# Camera_Module.net
KiCad netlist of a schematic drawn in Altium Designer
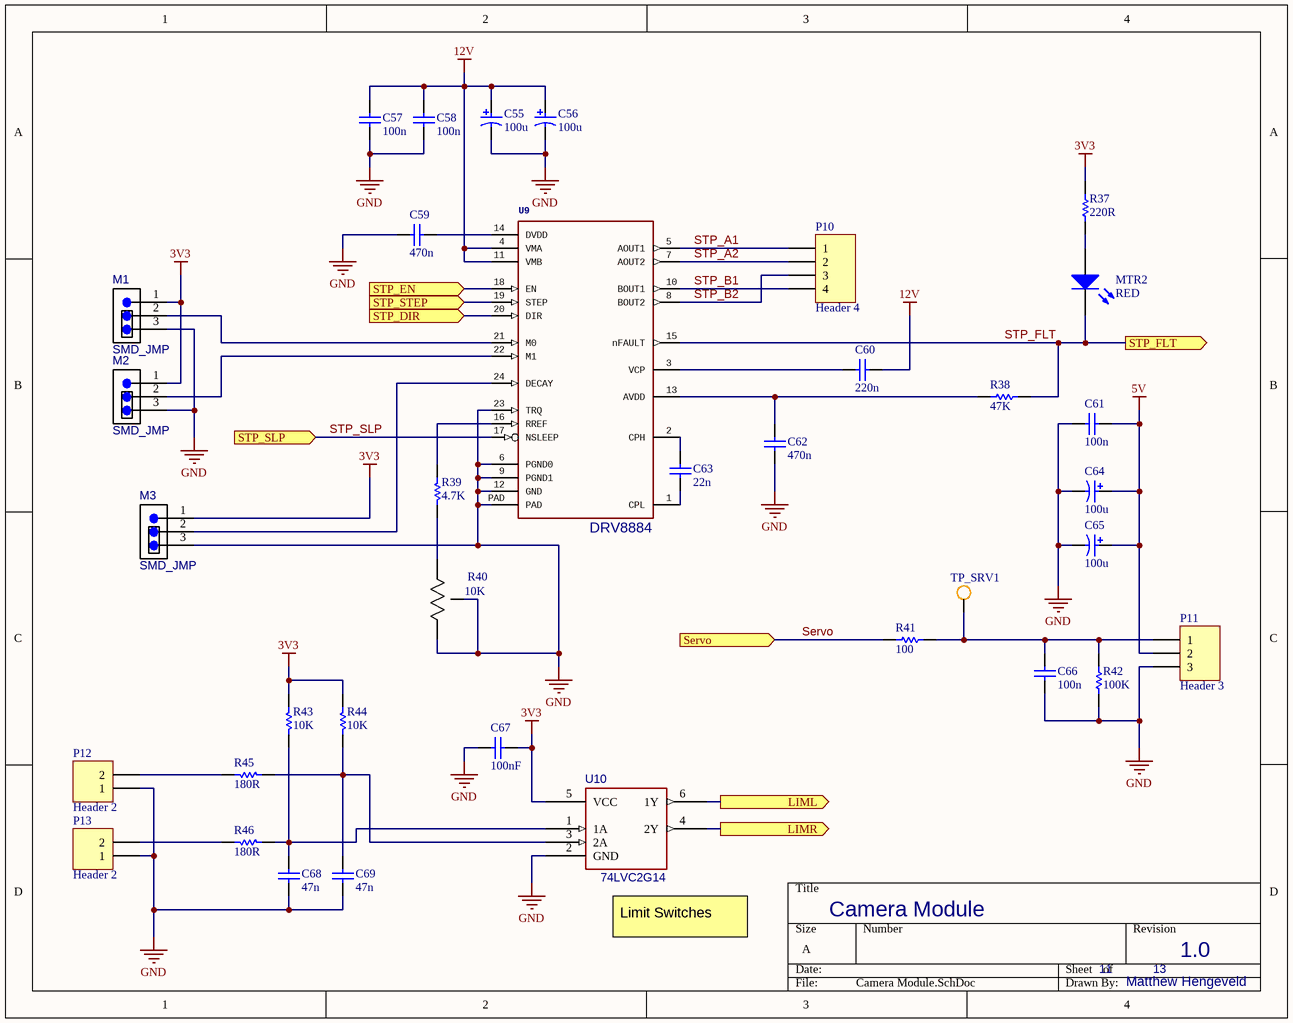
[diagram p0: Camera Module.SchDoc]

(export (version "E")
  (design (tool "Eeschema 10.0.6"))
  (components
    (comp (ref "C55")
      (value "100u")
      (footprint "SMD-CAP-0606")
      (fields (field (name "PARTNUMBER") "UUD1V101MNL1GS") (field (name "MANUFACTURER") "Nichicon"))
      (libsource (lib "Hengeveld") (part "CAP-EL-0606-SMD"))
    )
    (comp (ref "C56")
      (value "100u")
      (footprint "SMD-CAP-0606")
      (fields (field (name "PARTNUMBER") "UUD1V101MNL1GS") (field (name "MANUFACTURER") "Nichicon"))
      (libsource (lib "Hengeveld") (part "CAP-EL-0606-SMD"))
    )
    (comp (ref "C57")
      (value "100n")
      (footprint "CAPC1608X87X35LL15T15")
      (fields (field (name "PART NUMBER") "C0603X104K5RACTU") (field (name "MANUFACTURER") "Kemet"))
      (libsource (lib "Altium Content Vault") (part "CAP"))
    )
    (comp (ref "C58")
      (value "100n")
      (footprint "CAPC1608X87X35LL15T15")
      (fields (field (name "PART NUMBER") "C0603X104K5RACTU") (field (name "MANUFACTURER") "Kemet"))
      (libsource (lib "Altium Content Vault") (part "CAP"))
    )
    (comp (ref "C59")
      (value "470n")
      (footprint "CAPC1608X87X35LL15T15")
      (fields (field (name "PART NUMBER") "C0603X104K5RACTU") (field (name "MANUFACTURER") "Kemet"))
      (libsource (lib "Altium Content Vault") (part "CAP"))
    )
    (comp (ref "C60")
      (value "220n")
      (footprint "CAPC1608X87X35LL15T15")
      (fields (field (name "PART NUMBER") "C0603X104K5RACTU") (field (name "MANUFACTURER") "Kemet"))
      (libsource (lib "Altium Content Vault") (part "CAP"))
    )
    (comp (ref "C61")
      (value "100n")
      (footprint "CAPC1608X87X35LL15T15")
      (fields (field (name "PART NUMBER") "C0603X104K5RACTU") (field (name "MANUFACTURER") "Kemet"))
      (libsource (lib "Altium Content Vault") (part "CAP"))
    )
    (comp (ref "C62")
      (value "470n")
      (footprint "CAPC1608X90X35LL10T15")
      (fields (field (name "MANUFACTURER") "Murata") (field (name "PART NUMBER") "GRM188R71C474KA88D"))
      (libsource (lib "Altium Content Vault") (part "CAP"))
    )
    (comp (ref "C63")
      (value "22n")
      (footprint "CAPC1608X87X35LL15T15")
      (fields (field (name "MANUFACTURER") "Kemet") (field (name "PART NUMBER") "C0603C103K1RACTU"))
      (libsource (lib "Altium Content Vault") (part "CAP"))
    )
    (comp (ref "C64")
      (value "100u")
      (footprint "SMD-CAP-0606")
      (fields (field (name "PARTNUMBER") "UUD1V101MNL1GS") (field (name "MANUFACTURER") "Nichicon"))
      (libsource (lib "Hengeveld") (part "CAP-EL-0606-SMD"))
    )
    (comp (ref "C65")
      (value "100u")
      (footprint "SMD-CAP-0606")
      (fields (field (name "PARTNUMBER") "UUD1V101MNL1GS") (field (name "MANUFACTURER") "Nichicon"))
      (libsource (lib "Hengeveld") (part "CAP-EL-0606-SMD"))
    )
    (comp (ref "C66")
      (value "100n")
      (footprint "CAPC1608X90X35LL10T15")
      (fields (field (name "MANUFACTURER") "Murata") (field (name "PART NUMBER") "GRM188R71C474KA88D"))
      (libsource (lib "Altium Content Vault") (part "CAP"))
    )
    (comp (ref "C67")
      (value "100nF")
      (footprint "CAPC1608X92X38LL15T08")
      (fields (field (name "PART NUMBER") "VJ0603Y104KNXAO") (field (name "MANUFACTURER") "Vitramon"))
      (libsource (lib "Altium Content Vault") (part "CAP"))
    )
    (comp (ref "C68")
      (value "47n")
      (footprint "CAPC1608X87X35LL15T15")
      (fields (field (name "PART NUMBER") "C0603X104K5RACTU") (field (name "MANUFACTURER") "Kemet"))
      (libsource (lib "Altium Content Vault") (part "CAP"))
    )
    (comp (ref "C69")
      (value "47n")
      (footprint "CAPC1608X87X35LL15T15")
      (fields (field (name "PART NUMBER") "C0603X104K5RACTU") (field (name "MANUFACTURER") "Kemet"))
      (libsource (lib "Altium Content Vault") (part "CAP"))
    )
    (comp (ref "M1")
      (value "SMD_JMP")
      (footprint "0603_JUMPER")
      (libsource (lib "Hengeveld") (part "SMD_JMP"))
    )
    (comp (ref "M2")
      (value "SMD_JMP")
      (footprint "0603_JUMPER")
      (libsource (lib "Hengeveld") (part "SMD_JMP"))
    )
    (comp (ref "M3")
      (value "SMD_JMP")
      (footprint "0603_JUMPER")
      (libsource (lib "Hengeveld") (part "SMD_JMP"))
    )
    (comp (ref "MTR2")
      (value "RED")
      (footprint "0805_A")
      (description "SMD mono-color Chip LED, WL-SMCW, Red")
      (fields (field (name "PARTNUMBER") "150080RS75000") (field (name "MANUFACTURER") "Wuerth Elektronik"))
      (libsource (lib "Altium Content Vault") (part "WE-LED_K1A2-2"))
    )
    (comp (ref "P10")
      (value "Header 4")
      (footprint "HDR1X4")
      (description "Header, 4-Pin")
      (fields (field (name "PUBLISHER") "Altium Limited"))
      (libsource (lib "Hengeveld") (part "Header 4"))
    )
    (comp (ref "P11")
      (value "Header 3")
      (footprint "HDR1X3")
      (description "Header, 3-Pin")
      (fields (field (name "PUBLISHER") "Altium Limited"))
      (libsource (lib "Hengeveld") (part "Header 3"))
    )
    (comp (ref "P12")
      (value "Header 2")
      (footprint "HDR1X2")
      (description "Header, 2-Pin")
      (fields (field (name "PUBLISHER") "Altium Limited"))
      (libsource (lib "Hengeveld") (part "Header 2"))
    )
    (comp (ref "P13")
      (value "Header 2")
      (footprint "HDR1X2")
      (description "Header, 2-Pin")
      (fields (field (name "PUBLISHER") "Altium Limited"))
      (libsource (lib "Hengeveld") (part "Header 2"))
    )
    (comp (ref "R37")
      (value "220R")
      (footprint "RESC1608X55X30LL15T15")
      (fields (field (name "MANUFACTURER") "Panasonic") (field (name "PART NUMBER") "ERJ-3GEYJ103V"))
      (libsource (lib "Altium Content Vault") (part "RES"))
    )
    (comp (ref "R38")
      (value "47K")
      (footprint "RESC1608X55X30LL15T15")
      (fields (field (name "MANUFACTURER") "Panasonic") (field (name "PART NUMBER") "ERJ-3GEYJ103V"))
      (libsource (lib "Altium Content Vault") (part "RES"))
    )
    (comp (ref "R39")
      (value "4.7K")
      (footprint "RESC1608X55X30LL15T15")
      (fields (field (name "MANUFACTURER") "Panasonic") (field (name "PART NUMBER") "ERJ-3GEYJ103V"))
      (libsource (lib "Altium Content Vault") (part "RES"))
    )
    (comp (ref "R40") (value "10K") (footprint "TRIMMER-TC33") (libsource (lib "Hengeveld") (part "Trimmer")))
    (comp (ref "R41")
      (value "100")
      (footprint "RESC1608X55X30LL15T15")
      (fields (field (name "MANUFACTURER") "Panasonic") (field (name "PART NUMBER") "ERJ-3GEYJ103V"))
      (libsource (lib "Altium Content Vault") (part "RES"))
    )
    (comp (ref "R42")
      (value "100K")
      (footprint "RESC1608X55X30LL15T15")
      (fields (field (name "MANUFACTURER") "Panasonic") (field (name "PART NUMBER") "ERJ-3GEYJ103V"))
      (libsource (lib "Altium Content Vault") (part "RES"))
    )
    (comp (ref "R43")
      (value "10K")
      (footprint "RESC1608X55X30LL15T15")
      (fields (field (name "MANUFACTURER") "Panasonic") (field (name "PART NUMBER") "ERJ-3GEYJ103V"))
      (libsource (lib "Altium Content Vault") (part "RES"))
    )
    (comp (ref "R44")
      (value "10K")
      (footprint "RESC1608X55X30LL15T15")
      (fields (field (name "MANUFACTURER") "Panasonic") (field (name "PART NUMBER") "ERJ-3GEYJ103V"))
      (libsource (lib "Altium Content Vault") (part "RES"))
    )
    (comp (ref "R45")
      (value "180R")
      (footprint "RESC1608X55X30LL15T15")
      (fields (field (name "MANUFACTURER") "Panasonic") (field (name "PART NUMBER") "ERJ-3GEYJ103V"))
      (libsource (lib "Altium Content Vault") (part "RES"))
    )
    (comp (ref "R46")
      (value "180R")
      (footprint "RESC1608X55X30LL15T15")
      (fields (field (name "MANUFACTURER") "Panasonic") (field (name "PART NUMBER") "ERJ-3GEYJ103V"))
      (libsource (lib "Altium Content Vault") (part "RES"))
    )
    (comp (ref "TP_SRV1")
      (value "Test point")
      (footprint "SMD Test Hook")
      (libsource (lib "Hengeveld") (part "Test Point"))
    )
    (comp (ref "U9") (value "DRV8884") (footprint "TI-PWP24") (libsource (lib "Hengeveld") (part "DRV8884")))
    (comp (ref "U10")
      (value "74LVC2G14")
      (footprint "ONSC-SOT-363-6-419B-02_V")
      (libsource (lib "Hengeveld") (part "74LVC2G14"))
    )
  )
  (nets
    (net (code "1") (name "/LIML") (class "Default")
      (node (ref "U10") (pin "6") (pinfunction "1Y_6") (pintype "output"))
    )
    (net (code "2") (name "/LIMR") (class "Default")
      (node (ref "U10") (pin "4") (pinfunction "2Y_4") (pintype "output"))
    )
    (net (code "3") (name "/STP_A1") (class "Default")
      (node (ref "P10") (pin "1") (pinfunction "1_1") (pintype "passive"))
      (node (ref "U9") (pin "5") (pinfunction "AOUT1_5") (pintype "output"))
    )
    (net (code "4") (name "/STP_A2") (class "Default")
      (node (ref "P10") (pin "2") (pinfunction "2_2") (pintype "passive"))
      (node (ref "U9") (pin "7") (pinfunction "AOUT2_7") (pintype "output"))
    )
    (net (code "5") (name "/STP_B1") (class "Default")
      (node (ref "P10") (pin "4") (pinfunction "4_4") (pintype "passive"))
      (node (ref "U9") (pin "10") (pinfunction "BOUT1_10") (pintype "output"))
    )
    (net (code "6") (name "/STP_B2") (class "Default")
      (node (ref "P10") (pin "3") (pinfunction "3_3") (pintype "passive"))
      (node (ref "U9") (pin "8") (pinfunction "BOUT2_8") (pintype "output"))
    )
    (net (code "7") (name "/STP_DIR") (class "Default")
      (node (ref "U9") (pin "20") (pinfunction "DIR_20") (pintype "input"))
    )
    (net (code "8") (name "/STP_EN") (class "Default")
      (node (ref "U9") (pin "18") (pinfunction "EN_18") (pintype "input"))
    )
    (net (code "9") (name "/STP_FLT") (class "Default")
      (node (ref "MTR2") (pin "1") (pinfunction "K_1") (pintype "passive"))
      (node (ref "R38") (pin "2") (pinfunction "2_2") (pintype "passive"))
      (node (ref "U9") (pin "15") (pinfunction "nFAULT_15") (pintype "output"))
    )
    (net (code "10") (name "/STP_SLP") (class "Default")
      (node (ref "U9") (pin "17") (pinfunction "NSLEEP_17") (pintype "input"))
    )
    (net (code "11") (name "/STP_STEP") (class "Default")
      (node (ref "U9") (pin "19") (pinfunction "STEP_19") (pintype "input"))
    )
    (net (code "12") (name "/Servo") (class "Default")
      (node (ref "R41") (pin "2") (pinfunction "2_2") (pintype "passive"))
    )
    (net (code "13") (name "3V3") (class "Default")
      (node (ref "C67") (pin "2") (pinfunction "2_2") (pintype "passive"))
      (node (ref "M1") (pin "1") (pinfunction "1_1") (pintype "passive"))
      (node (ref "M2") (pin "1") (pinfunction "1_1") (pintype "passive"))
      (node (ref "M3") (pin "1") (pinfunction "1_1") (pintype "passive"))
      (node (ref "R37") (pin "1") (pinfunction "1_1") (pintype "passive"))
      (node (ref "R43") (pin "1") (pinfunction "1_1") (pintype "passive"))
      (node (ref "R44") (pin "1") (pinfunction "1_1") (pintype "passive"))
      (node (ref "U10") (pin "5") (pinfunction "VCC_5") (pintype "power_in"))
    )
    (net (code "14") (name "5V") (class "Default")
      (node (ref "C61") (pin "1") (pinfunction "1_1") (pintype "passive"))
      (node (ref "C64") (pin "1") (pinfunction "1_1") (pintype "passive"))
      (node (ref "C65") (pin "1") (pinfunction "1_1") (pintype "passive"))
      (node (ref "P11") (pin "2") (pinfunction "2_2") (pintype "passive"))
    )
    (net (code "15") (name "12V") (class "Default")
      (node (ref "C55") (pin "1") (pinfunction "1_1") (pintype "passive"))
      (node (ref "C56") (pin "1") (pinfunction "1_1") (pintype "passive"))
      (node (ref "C57") (pin "2") (pinfunction "2_2") (pintype "passive"))
      (node (ref "C58") (pin "2") (pinfunction "2_2") (pintype "passive"))
      (node (ref "C60") (pin "1") (pinfunction "1_1") (pintype "passive"))
      (node (ref "U9") (pin "11") (pinfunction "VMB_11") (pintype "power_in"))
      (node (ref "U9") (pin "4") (pinfunction "VMA_4") (pintype "power_in"))
    )
    (net (code "16") (name "GND") (class "Default")
      (node (ref "C55") (pin "2") (pinfunction "2_2") (pintype "passive"))
      (node (ref "C56") (pin "2") (pinfunction "2_2") (pintype "passive"))
      (node (ref "C57") (pin "1") (pinfunction "1_1") (pintype "passive"))
      (node (ref "C58") (pin "1") (pinfunction "1_1") (pintype "passive"))
      (node (ref "C59") (pin "2") (pinfunction "2_2") (pintype "passive"))
      (node (ref "C61") (pin "2") (pinfunction "2_2") (pintype "passive"))
      (node (ref "C62") (pin "1") (pinfunction "1_1") (pintype "passive"))
      (node (ref "C64") (pin "2") (pinfunction "2_2") (pintype "passive"))
      (node (ref "C65") (pin "2") (pinfunction "2_2") (pintype "passive"))
      (node (ref "C66") (pin "1") (pinfunction "1_1") (pintype "passive"))
      (node (ref "C67") (pin "1") (pinfunction "1_1") (pintype "passive"))
      (node (ref "C68") (pin "2") (pinfunction "2_2") (pintype "passive"))
      (node (ref "C69") (pin "2") (pinfunction "2_2") (pintype "passive"))
      (node (ref "M1") (pin "3") (pinfunction "3_3") (pintype "passive"))
      (node (ref "M2") (pin "3") (pinfunction "3_3") (pintype "passive"))
      (node (ref "M3") (pin "3") (pinfunction "3_3") (pintype "passive"))
      (node (ref "P11") (pin "3") (pinfunction "3_3") (pintype "passive"))
      (node (ref "P12") (pin "1") (pinfunction "1_1") (pintype "passive"))
      (node (ref "P13") (pin "1") (pinfunction "1_1") (pintype "passive"))
      (node (ref "R40") (pin "2") (pinfunction "2_2") (pintype "passive"))
      (node (ref "R40") (pin "3") (pinfunction "3_3") (pintype "passive"))
      (node (ref "R42") (pin "2") (pinfunction "2_2") (pintype "passive"))
      (node (ref "U10") (pin "2") (pinfunction "GND_2") (pintype "power_in"))
      (node (ref "U9") (pin "12") (pinfunction "GND_12") (pintype "power_in"))
      (node (ref "U9") (pin "23") (pinfunction "TRQ_23") (pintype "input"))
      (node (ref "U9") (pin "6") (pinfunction "PGND0_6") (pintype "power_in"))
      (node (ref "U9") (pin "9") (pinfunction "PGND1_9") (pintype "power_in"))
      (node (ref "U9") (pin "PAD") (pinfunction "PAD_PAD") (pintype "power_in"))
    )
    (net (code "17") (name "Net-(MTR2-A)") (class "Default")
      (node (ref "MTR2") (pin "2") (pinfunction "A_2") (pintype "passive"))
      (node (ref "R37") (pin "2") (pinfunction "2_2") (pintype "passive"))
    )
    (net (code "18") (name "Net-(P12-Pad2)") (class "Default")
      (node (ref "P12") (pin "2") (pinfunction "2_2") (pintype "passive"))
      (node (ref "R45") (pin "1") (pinfunction "1_1") (pintype "passive"))
    )
    (net (code "19") (name "Net-(P13-Pad2)") (class "Default")
      (node (ref "P13") (pin "2") (pinfunction "2_2") (pintype "passive"))
      (node (ref "R46") (pin "1") (pinfunction "1_1") (pintype "passive"))
    )
    (net (code "20") (name "Net-(R39-Pad2)") (class "Default")
      (node (ref "R39") (pin "2") (pinfunction "2_2") (pintype "passive"))
      (node (ref "R40") (pin "1") (pinfunction "1_1") (pintype "passive"))
    )
    (net (code "21") (name "Net-(TP_SRV1-point)") (class "Default")
      (node (ref "C66") (pin "2") (pinfunction "2_2") (pintype "passive"))
      (node (ref "P11") (pin "1") (pinfunction "1_1") (pintype "passive"))
      (node (ref "R41") (pin "1") (pinfunction "1_1") (pintype "passive"))
      (node (ref "R42") (pin "1") (pinfunction "1_1") (pintype "passive"))
      (node (ref "TP_SRV1") (pin "1") (pinfunction "point_1") (pintype "passive"))
    )
    (net (code "22") (name "Net-(U9-AVDD)") (class "Default")
      (node (ref "C62") (pin "2") (pinfunction "2_2") (pintype "passive"))
      (node (ref "R38") (pin "1") (pinfunction "1_1") (pintype "passive"))
      (node (ref "U9") (pin "13") (pinfunction "AVDD_13") (pintype "power_in"))
    )
    (net (code "23") (name "Net-(U9-CPH)") (class "Default")
      (node (ref "C63") (pin "2") (pinfunction "2_2") (pintype "passive"))
      (node (ref "U9") (pin "2") (pinfunction "CPH_2") (pintype "power_in"))
    )
    (net (code "24") (name "Net-(U9-CPL)") (class "Default")
      (node (ref "C63") (pin "1") (pinfunction "1_1") (pintype "passive"))
      (node (ref "U9") (pin "1") (pinfunction "CPL_1") (pintype "power_in"))
    )
    (net (code "25") (name "Net-(U9-DECAY)") (class "Default")
      (node (ref "M3") (pin "2") (pinfunction "2_2") (pintype "passive"))
      (node (ref "U9") (pin "24") (pinfunction "DECAY_24") (pintype "input"))
    )
    (net (code "26") (name "Net-(U9-DVDD)") (class "Default")
      (node (ref "C59") (pin "1") (pinfunction "1_1") (pintype "passive"))
      (node (ref "U9") (pin "14") (pinfunction "DVDD_14") (pintype "power_in"))
    )
    (net (code "27") (name "Net-(U9-M0)") (class "Default")
      (node (ref "M1") (pin "2") (pinfunction "2_2") (pintype "passive"))
      (node (ref "U9") (pin "21") (pinfunction "M0_21") (pintype "input"))
    )
    (net (code "28") (name "Net-(U9-M1)") (class "Default")
      (node (ref "M2") (pin "2") (pinfunction "2_2") (pintype "passive"))
      (node (ref "U9") (pin "22") (pinfunction "M1_22") (pintype "input"))
    )
    (net (code "29") (name "Net-(U9-RREF)") (class "Default")
      (node (ref "R39") (pin "1") (pinfunction "1_1") (pintype "passive"))
      (node (ref "U9") (pin "16") (pinfunction "RREF_16") (pintype "input"))
    )
    (net (code "30") (name "Net-(U9-VCP)") (class "Default")
      (node (ref "C60") (pin "2") (pinfunction "2_2") (pintype "passive"))
      (node (ref "U9") (pin "3") (pinfunction "VCP_3") (pintype "power_in"))
    )
    (net (code "31") (name "Net-(U10-1A)") (class "Default")
      (node (ref "C68") (pin "1") (pinfunction "1_1") (pintype "passive"))
      (node (ref "R43") (pin "2") (pinfunction "2_2") (pintype "passive"))
      (node (ref "R46") (pin "2") (pinfunction "2_2") (pintype "passive"))
      (node (ref "U10") (pin "1") (pinfunction "1A_1") (pintype "input"))
    )
    (net (code "32") (name "Net-(U10-2A)") (class "Default")
      (node (ref "C69") (pin "1") (pinfunction "1_1") (pintype "passive"))
      (node (ref "R44") (pin "2") (pinfunction "2_2") (pintype "passive"))
      (node (ref "R45") (pin "2") (pinfunction "2_2") (pintype "passive"))
      (node (ref "U10") (pin "3") (pinfunction "2A_3") (pintype "input"))
    )
  )
)
